# SHT_Test_Module.net
KiCad netlist of a schematic drawn in EAGLE
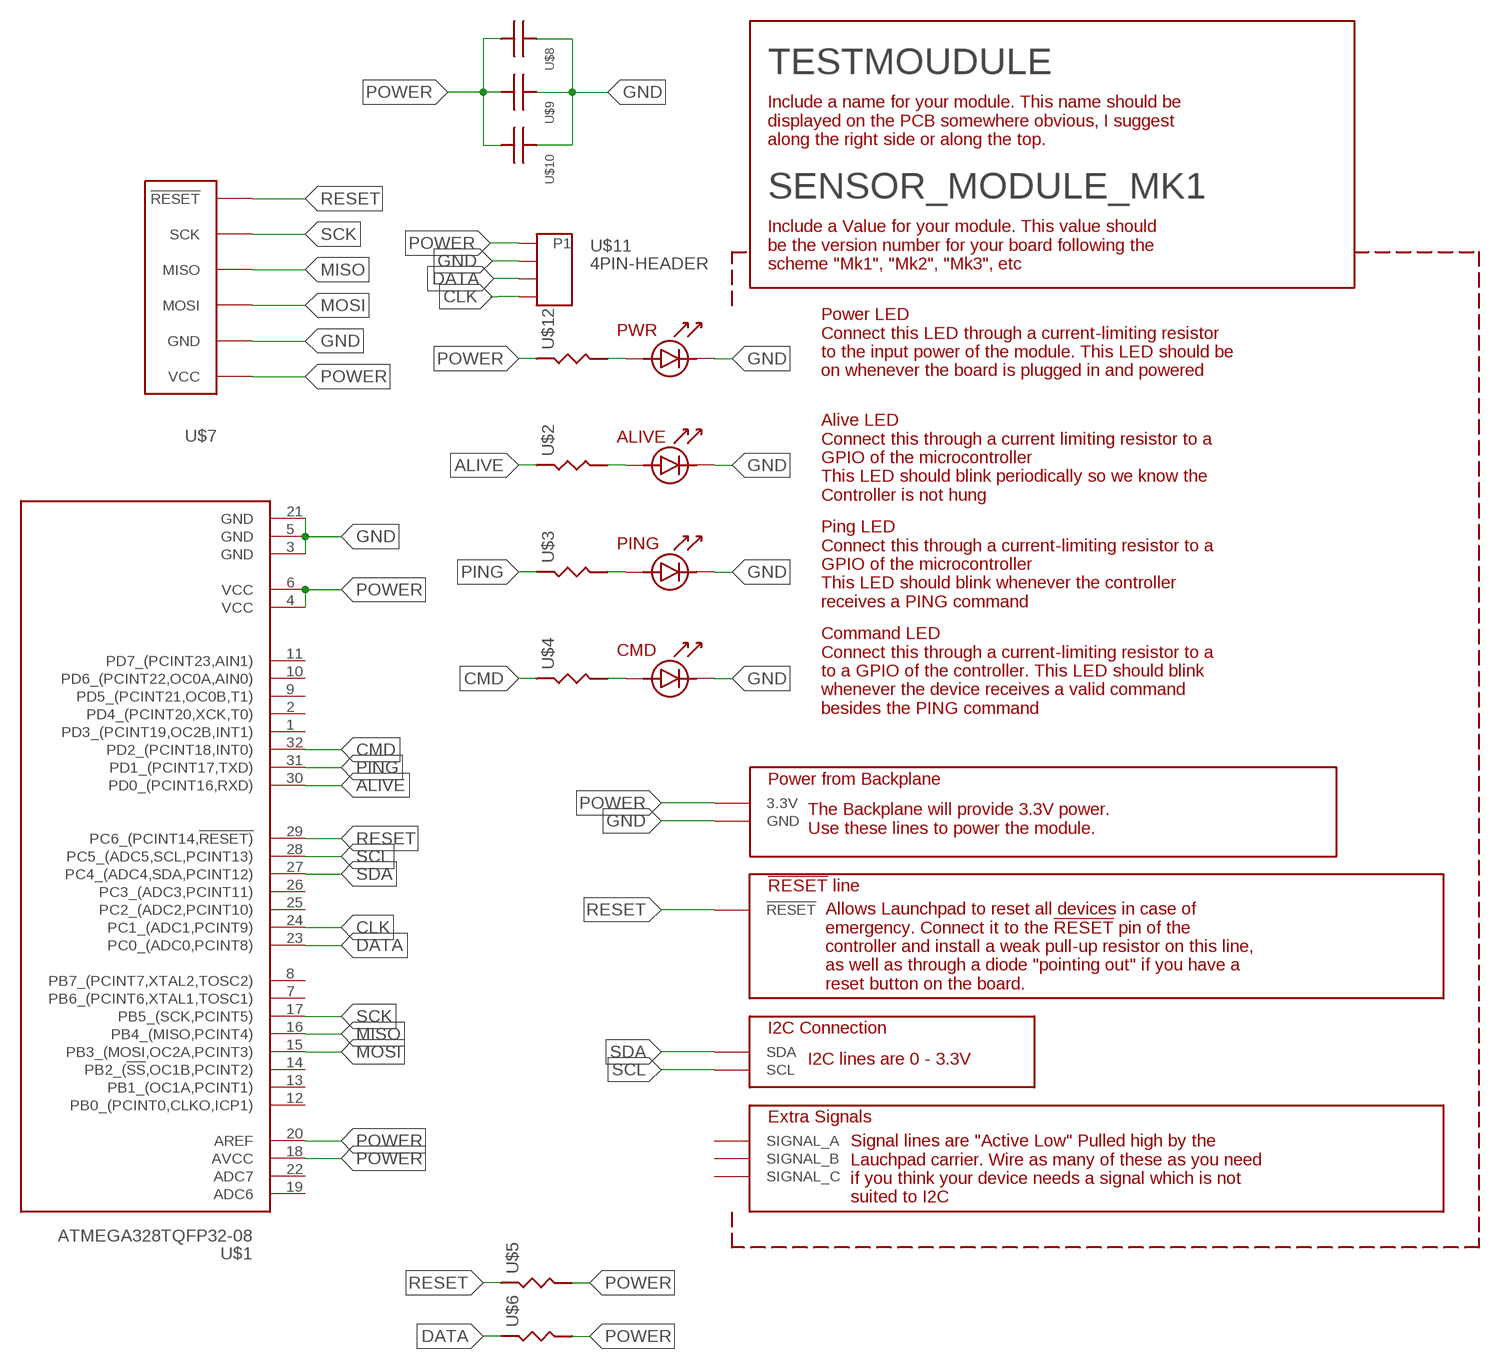
[diagram p0: schematic, sheet 1]

(export (version "E")
  (design (tool "Eeschema 10.0.6"))
  (components
    (comp (ref "TESTMOUDULE")
      (value "SENSOR_MODULE_MK1")
      (footprint "eagle-import:SENSOR_MODULE_MK1")
      (libsource (lib "eagle-import") (part "SENSOR_MODULE_MK1"))
    )
    (comp (ref "U$1")
      (value "ATMEGA328TQFP32-08")
      (footprint "eagle-import:TQFP32-08")
      (libsource (lib "eagle-import") (part "ATMEGA328TQFP32-08"))
    )
    (comp (ref "U$2")
      (value "RESISTOR")
      (footprint "eagle-import:0805_STACKPOLERESISTOR")
      (libsource (lib "eagle-import") (part "RESISTOR"))
    )
    (comp (ref "U$3")
      (value "RESISTOR")
      (footprint "eagle-import:0805_STACKPOLERESISTOR")
      (libsource (lib "eagle-import") (part "RESISTOR"))
    )
    (comp (ref "U$4")
      (value "RESISTOR")
      (footprint "eagle-import:0805_STACKPOLERESISTOR")
      (libsource (lib "eagle-import") (part "RESISTOR"))
    )
    (comp (ref "U$5")
      (value "RESISTOR")
      (footprint "eagle-import:0805_STACKPOLERESISTOR")
      (libsource (lib "eagle-import") (part "RESISTOR"))
    )
    (comp (ref "U$6")
      (value "RESISTOR")
      (footprint "eagle-import:0805_STACKPOLERESISTOR")
      (libsource (lib "eagle-import") (part "RESISTOR"))
    )
    (comp (ref "U$7")
      (value "ISP_PROGRAMMING_HEADER")
      (footprint "eagle-import:6PINHEADER_CORRECT")
      (libsource (lib "eagle-import") (part "ISP_PROGRAMMING_HEADER"))
    )
    (comp (ref "U$8")
      (value "CAPACITOR-UNPOLARIZED0805")
      (footprint "eagle-import:0805_STACKPOLERESISTOR")
      (libsource (lib "eagle-import") (part "CAPACITOR-UNPOLARIZED0805"))
    )
    (comp (ref "U$9")
      (value "CAPACITOR-UNPOLARIZED0805")
      (footprint "eagle-import:0805_STACKPOLERESISTOR")
      (libsource (lib "eagle-import") (part "CAPACITOR-UNPOLARIZED0805"))
    )
    (comp (ref "U$10")
      (value "CAPACITOR-UNPOLARIZED0805")
      (footprint "eagle-import:0805_STACKPOLERESISTOR")
      (libsource (lib "eagle-import") (part "CAPACITOR-UNPOLARIZED0805"))
    )
    (comp (ref "U$11")
      (value "4PIN-HEADER")
      (footprint "eagle-import:4HEADER_10MIL")
      (libsource (lib "eagle-import") (part "4PIN-HEADER"))
    )
    (comp (ref "U$12")
      (value "RESISTOR")
      (footprint "eagle-import:0805_STACKPOLERESISTOR")
      (libsource (lib "eagle-import") (part "RESISTOR"))
    )
  )
  (nets
    (net (code "1") (name "ALIVE") (class "Default")
      (node (ref "U$1") (pin "30") (pinfunction "PD0_(PCINT16,RXD)_30") (pintype "bidirectional"))
      (node (ref "U$2") (pin "P$1") (pinfunction "P$1_P$1") (pintype "bidirectional"))
    )
    (net (code "2") (name "CLK") (class "Default")
      (node (ref "U$1") (pin "24") (pinfunction "PC1_(ADC1,PCINT9)_24") (pintype "bidirectional"))
      (node (ref "U$11") (pin "P$4") (pinfunction "P$4_P$4") (pintype "bidirectional"))
    )
    (net (code "3") (name "CMD") (class "Default")
      (node (ref "U$1") (pin "32") (pinfunction "PD2_(PCINT18,INT0)_32") (pintype "bidirectional"))
      (node (ref "U$4") (pin "P$1") (pinfunction "P$1_P$1") (pintype "bidirectional"))
    )
    (net (code "4") (name "DATA") (class "Default")
      (node (ref "U$1") (pin "23") (pinfunction "PC0_(ADC0,PCINT8)_23") (pintype "bidirectional"))
      (node (ref "U$11") (pin "P$3") (pinfunction "P$3_P$3") (pintype "bidirectional"))
      (node (ref "U$6") (pin "P$1") (pinfunction "P$1_P$1") (pintype "bidirectional"))
    )
    (net (code "5") (name "GND") (class "Default")
      (node (ref "TESTMOUDULE") (pin "ALIVELED_CATHODE") (pinfunction "ALIVELED_CATHODE_ALIVELED_CATHODE") (pintype "bidirectional"))
      (node (ref "TESTMOUDULE") (pin "CMDLED_CATHODE") (pinfunction "CMDLED_CATHODE_CMDLED_CATHODE") (pintype "bidirectional"))
      (node (ref "TESTMOUDULE") (pin "GND") (pinfunction "GND_GND") (pintype "bidirectional"))
      (node (ref "TESTMOUDULE") (pin "PINGLED_CATHODE") (pinfunction "PINGLED_CATHODE_PINGLED_CATHODE") (pintype "bidirectional"))
      (node (ref "TESTMOUDULE") (pin "PWRLED_CATHODE") (pinfunction "PWRLED_CATHODE_PWRLED_CATHODE") (pintype "bidirectional"))
      (node (ref "U$1") (pin "21") (pinfunction "GND_21") (pintype "bidirectional"))
      (node (ref "U$1") (pin "3") (pinfunction "GND_3") (pintype "bidirectional"))
      (node (ref "U$1") (pin "5") (pinfunction "GND_5") (pintype "bidirectional"))
      (node (ref "U$10") (pin "P$1") (pinfunction "P$1_P$1") (pintype "bidirectional"))
      (node (ref "U$11") (pin "P$2") (pinfunction "P$2_P$2") (pintype "bidirectional"))
      (node (ref "U$7") (pin "6") (pinfunction "GND_6") (pintype "bidirectional"))
      (node (ref "U$8") (pin "P$1") (pinfunction "P$1_P$1") (pintype "bidirectional"))
      (node (ref "U$9") (pin "P$1") (pinfunction "P$1_P$1") (pintype "bidirectional"))
    )
    (net (code "6") (name "MISO") (class "Default")
      (node (ref "U$1") (pin "16") (pinfunction "PB4_(MISO,PCINT4)_16") (pintype "bidirectional"))
      (node (ref "U$7") (pin "1") (pinfunction "MISO_1") (pintype "bidirectional"))
    )
    (net (code "7") (name "MOSI") (class "Default")
      (node (ref "U$1") (pin "15") (pinfunction "PB3_(MOSI,OC2A,PCINT3)_15") (pintype "bidirectional"))
      (node (ref "U$7") (pin "4") (pinfunction "MOSI_4") (pintype "bidirectional"))
    )
    (net (code "8") (name "Net-(TESTMOUDULE-PadALIVELED_ANODE)") (class "Default")
      (node (ref "TESTMOUDULE") (pin "ALIVELED_ANODE") (pinfunction "ALIVELED_ANODE_ALIVELED_ANODE") (pintype "bidirectional"))
      (node (ref "U$2") (pin "P$2") (pinfunction "P$2_P$2") (pintype "bidirectional"))
    )
    (net (code "9") (name "Net-(TESTMOUDULE-PadCMDLED_ANODE)") (class "Default")
      (node (ref "TESTMOUDULE") (pin "CMDLED_ANODE") (pinfunction "CMDLED_ANODE_CMDLED_ANODE") (pintype "bidirectional"))
      (node (ref "U$4") (pin "P$2") (pinfunction "P$2_P$2") (pintype "bidirectional"))
    )
    (net (code "10") (name "Net-(TESTMOUDULE-PadPINGLED_ANODE)") (class "Default")
      (node (ref "TESTMOUDULE") (pin "PINGLED_ANODE") (pinfunction "PINGLED_ANODE_PINGLED_ANODE") (pintype "bidirectional"))
      (node (ref "U$3") (pin "P$2") (pinfunction "P$2_P$2") (pintype "bidirectional"))
    )
    (net (code "11") (name "Net-(TESTMOUDULE-PadPWRLED_ANODE)") (class "Default")
      (node (ref "TESTMOUDULE") (pin "PWRLED_ANODE") (pinfunction "PWRLED_ANODE_PWRLED_ANODE") (pintype "bidirectional"))
      (node (ref "U$12") (pin "P$2") (pinfunction "P$2_P$2") (pintype "bidirectional"))
    )
    (net (code "12") (name "PING") (class "Default")
      (node (ref "U$1") (pin "31") (pinfunction "PD1_(PCINT17,TXD)_31") (pintype "bidirectional"))
      (node (ref "U$3") (pin "P$1") (pinfunction "P$1_P$1") (pintype "bidirectional"))
    )
    (net (code "13") (name "POWER") (class "Default")
      (node (ref "TESTMOUDULE") (pin "3P3V") (pinfunction "3.3V_3P3V") (pintype "bidirectional"))
      (node (ref "U$1") (pin "18") (pinfunction "AVCC_18") (pintype "bidirectional"))
      (node (ref "U$1") (pin "20") (pinfunction "AREF_20") (pintype "bidirectional"))
      (node (ref "U$1") (pin "4") (pinfunction "VCC_4") (pintype "bidirectional"))
      (node (ref "U$1") (pin "6") (pinfunction "VCC_6") (pintype "bidirectional"))
      (node (ref "U$10") (pin "P$2") (pinfunction "P$2_P$2") (pintype "bidirectional"))
      (node (ref "U$11") (pin "P$1") (pinfunction "P1_P$1") (pintype "bidirectional"))
      (node (ref "U$12") (pin "P$1") (pinfunction "P$1_P$1") (pintype "bidirectional"))
      (node (ref "U$5") (pin "P$2") (pinfunction "P$2_P$2") (pintype "bidirectional"))
      (node (ref "U$6") (pin "P$2") (pinfunction "P$2_P$2") (pintype "bidirectional"))
      (node (ref "U$7") (pin "2") (pinfunction "VCC_2") (pintype "bidirectional"))
      (node (ref "U$8") (pin "P$2") (pinfunction "P$2_P$2") (pintype "bidirectional"))
      (node (ref "U$9") (pin "P$2") (pinfunction "P$2_P$2") (pintype "bidirectional"))
    )
    (net (code "14") (name "RESET") (class "Default")
      (node (ref "TESTMOUDULE") (pin "RESET") (pinfunction "~{RESET}_RESET") (pintype "bidirectional"))
      (node (ref "U$1") (pin "29") (pinfunction "PC6_(PCINT14,~{RESET})_29") (pintype "bidirectional"))
      (node (ref "U$5") (pin "P$1") (pinfunction "P$1_P$1") (pintype "bidirectional"))
      (node (ref "U$7") (pin "5") (pinfunction "~{RESET}_5") (pintype "bidirectional"))
    )
    (net (code "15") (name "SCK") (class "Default")
      (node (ref "U$1") (pin "17") (pinfunction "PB5_(SCK,PCINT5)_17") (pintype "bidirectional"))
      (node (ref "U$7") (pin "3") (pinfunction "SCK_3") (pintype "bidirectional"))
    )
    (net (code "16") (name "SCL") (class "Default")
      (node (ref "TESTMOUDULE") (pin "SCL") (pinfunction "SCL_SCL") (pintype "bidirectional"))
      (node (ref "U$1") (pin "28") (pinfunction "PC5_(ADC5,SCL,PCINT13)_28") (pintype "bidirectional"))
    )
    (net (code "17") (name "SDA") (class "Default")
      (node (ref "TESTMOUDULE") (pin "SDA") (pinfunction "SDA_SDA") (pintype "bidirectional"))
      (node (ref "U$1") (pin "27") (pinfunction "PC4_(ADC4,SDA,PCINT12)_27") (pintype "bidirectional"))
    )
    (net (code "18") (name "unconnected-(TESTMOUDULE-SIGNAL_A-PadA)") (class "Default")
      (node (ref "TESTMOUDULE") (pin "A") (pinfunction "SIGNAL_A_A") (pintype "bidirectional"))
    )
    (net (code "19") (name "unconnected-(TESTMOUDULE-SIGNAL_B-PadB)") (class "Default")
      (node (ref "TESTMOUDULE") (pin "B") (pinfunction "SIGNAL_B_B") (pintype "bidirectional"))
    )
    (net (code "20") (name "unconnected-(TESTMOUDULE-SIGNAL_C-PadC)") (class "Default")
      (node (ref "TESTMOUDULE") (pin "C") (pinfunction "SIGNAL_C_C") (pintype "bidirectional"))
    )
    (net (code "21") (name "unconnected-(U$1-ADC6-Pad19)") (class "Default")
      (node (ref "U$1") (pin "19") (pinfunction "ADC6_19") (pintype "bidirectional"))
    )
    (net (code "22") (name "unconnected-(U$1-ADC7-Pad22)") (class "Default")
      (node (ref "U$1") (pin "22") (pinfunction "ADC7_22") (pintype "bidirectional"))
    )
    (net (code "23") (name "unconnected-(U$1-PB0_(PCINT0,CLKO,ICP1)-Pad12)") (class "Default")
      (node (ref "U$1") (pin "12") (pinfunction "PB0_(PCINT0,CLKO,ICP1)_12") (pintype "bidirectional"))
    )
    (net (code "24") (name "unconnected-(U$1-PB1_(OC1A,PCINT1)-Pad13)") (class "Default")
      (node (ref "U$1") (pin "13") (pinfunction "PB1_(OC1A,PCINT1)_13") (pintype "bidirectional"))
    )
    (net (code "25") (name "unconnected-(U$1-PB2_(~{SS,OC1B,PCINT2})-Pad14)") (class "Default")
      (node (ref "U$1") (pin "14") (pinfunction "PB2_(~{SS,OC1B,PCINT2})_14") (pintype "bidirectional"))
    )
    (net (code "26") (name "unconnected-(U$1-PB6_(PCINT6,XTAL1,TOSC1)-Pad7)") (class "Default")
      (node (ref "U$1") (pin "7") (pinfunction "PB6_(PCINT6,XTAL1,TOSC1)_7") (pintype "bidirectional"))
    )
    (net (code "27") (name "unconnected-(U$1-PB7_(PCINT7,XTAL2,TOSC2)-Pad8)") (class "Default")
      (node (ref "U$1") (pin "8") (pinfunction "PB7_(PCINT7,XTAL2,TOSC2)_8") (pintype "bidirectional"))
    )
    (net (code "28") (name "unconnected-(U$1-PC2_(ADC2,PCINT10)-Pad25)") (class "Default")
      (node (ref "U$1") (pin "25") (pinfunction "PC2_(ADC2,PCINT10)_25") (pintype "bidirectional"))
    )
    (net (code "29") (name "unconnected-(U$1-PC3_(ADC3,PCINT11)-Pad26)") (class "Default")
      (node (ref "U$1") (pin "26") (pinfunction "PC3_(ADC3,PCINT11)_26") (pintype "bidirectional"))
    )
    (net (code "30") (name "unconnected-(U$1-PD3_(PCINT19,OC2B,INT1)-Pad1)") (class "Default")
      (node (ref "U$1") (pin "1") (pinfunction "PD3_(PCINT19,OC2B,INT1)_1") (pintype "bidirectional"))
    )
    (net (code "31") (name "unconnected-(U$1-PD4_(PCINT20,XCK,T0)-Pad2)") (class "Default")
      (node (ref "U$1") (pin "2") (pinfunction "PD4_(PCINT20,XCK,T0)_2") (pintype "bidirectional"))
    )
    (net (code "32") (name "unconnected-(U$1-PD5_(PCINT21,OC0B,T1)-Pad9)") (class "Default")
      (node (ref "U$1") (pin "9") (pinfunction "PD5_(PCINT21,OC0B,T1)_9") (pintype "bidirectional"))
    )
    (net (code "33") (name "unconnected-(U$1-PD6_(PCINT22,OC0A,AIN0)-Pad10)") (class "Default")
      (node (ref "U$1") (pin "10") (pinfunction "PD6_(PCINT22,OC0A,AIN0)_10") (pintype "bidirectional"))
    )
    (net (code "34") (name "unconnected-(U$1-PD7_(PCINT23,AIN1)-Pad11)") (class "Default")
      (node (ref "U$1") (pin "11") (pinfunction "PD7_(PCINT23,AIN1)_11") (pintype "bidirectional"))
    )
  )
)
